# Main.net
KiCad netlist of a schematic drawn in Altium Designer
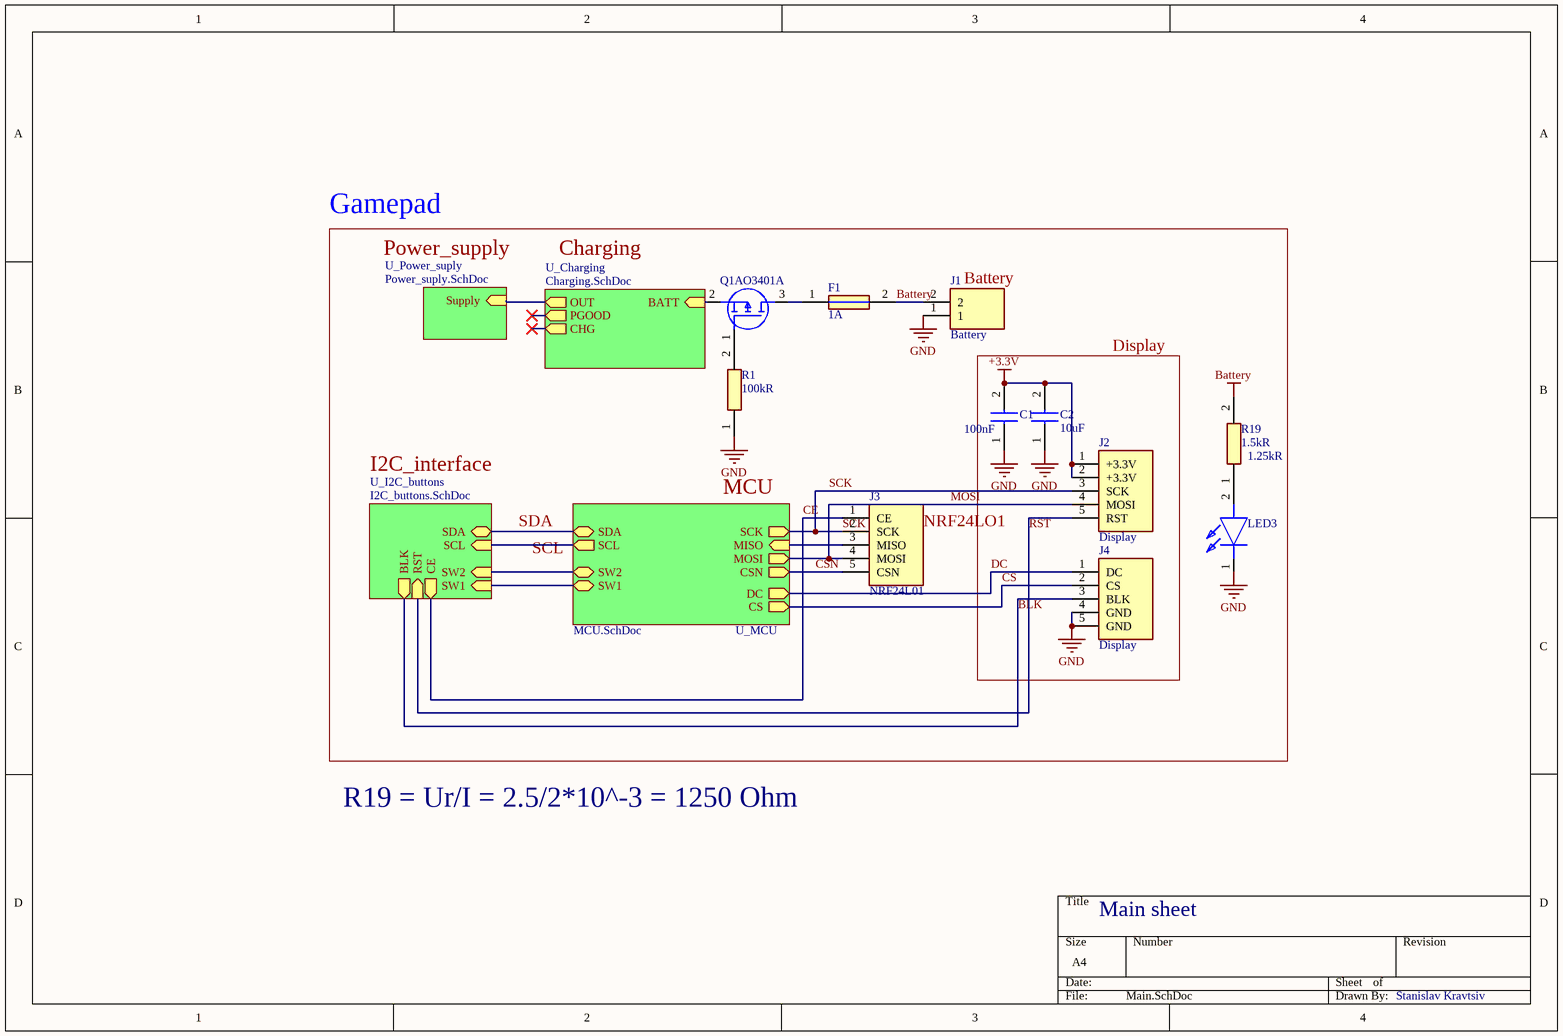
[diagram p0: Main.SchDoc]

(export (version "E")
  (design (tool "Eeschema 10.0.6"))
  (components
    (comp (ref "C1")
      (value "100nF")
      (footprint "SamacSys:CAPC1608X95N")
      (description "Capacitor")
      (fields
        (field (name "MANUFACTURER_PART_NUMBER") "0603B104K500CT")
        (field (name "MOUSER PART NUMBER") "791-0603B104K500CT")
      )
      (libsource (lib "*") (part "0603B104K500CT"))
    )
    (comp (ref "C2")
      (value "10uF")
      (footprint "SamacSys:CAPC2012X140N")
      (description "Capacitor")
      (fields
        (field (name "MANUFACTURER_PART_NUMBER") "CL21B106KPQNNNG")
        (field (name "MOUSER PART NUMBER") "187-CL21B106KPQNNNG")
      )
      (libsource (lib "*") (part "CL21B106KPQNNNG"))
    )
    (comp (ref "F1")
      (value "1А")
      (footprint "SamacSys:FUSC6125X279N")
      (description "Fuse")
      (fields
        (field (name "MANUFACTURER_PART_NUMBER") "0679L2000-01")
        (field (name "MOUSER PART NUMBER") "530-0679L2000-01")
      )
      (libsource (lib "*") (part "0679L2000-01"))
    )
    (comp (ref "J1")
      (value "Battery")
      (footprint "Conector_2")
      (description "Connector")
      (fields
        (field (name "MANUFACTURER_PART_NUMBER") "B2B-XH-AM(LF)(SN)")
        (field (name "MOUSER PART NUMBER") "306-B2B-XH-AMLFSNP")
      )
      (libsource (lib "Gamepad_schem_lib") (part "B2B-XH-AM_LF__SN_"))
    )
    (comp (ref "J2")
      (value "Display")
      (footprint "1.25_JSH-GH_5")
      (description "Connector")
      (fields (field (name "MANUFACTURER_PART_NUMBER") "B5B-XH-AM (LF)(SN)"))
      (libsource (lib "Gamepad_schem_lib") (part "B5B-XH-AM__LF__SN_"))
    )
    (comp (ref "J3")
      (value "NRF24L01")
      (footprint "1.25_JSH-GH_5")
      (description "Connector")
      (fields (field (name "MANUFACTURER_PART_NUMBER") "B5B-XH-AM (LF)(SN)"))
      (libsource (lib "Gamepad_schem_lib") (part "B5B-XH-AM__LF__SN_"))
    )
    (comp (ref "J4")
      (value "Display")
      (footprint "1.25_JSH-GH_5")
      (description "Connector")
      (fields (field (name "MANUFACTURER_PART_NUMBER") "B5B-XH-AM (LF)(SN)"))
      (libsource (lib "Gamepad_schem_lib") (part "B5B-XH-AM__LF__SN_"))
    )
    (comp (ref "LED3")
      (value "LS_L29K-H1J2-1")
      (footprint "SamacSys:SMT-0603")
      (description "LED")
      (fields
        (field (name "MANUFACTURER_PART_NUMBER") "LS L29K-H1J2-1")
        (field (name "MOUSER PART NUMBER") "720-LSL29K-H1J2-1-Z")
      )
      (libsource (lib "*") (part "LS_L29K-H1J2-1"))
    )
    (comp (ref "Q1")
      (value "AO3401A")
      (footprint "SamacSys:SOT95P280X125-3N")
      (description "MOSFET (P-Channel)")
      (libsource (lib "*") (part "AO3401A"))
    )
    (comp (ref "R1")
      (value "100kR")
      (footprint "SamacSys:RESC1608X55N")
      (description "Resistor")
      (fields
        (field (name "MANUFACTURER_PART_NUMBER") "RC0603FR-07100KL")
        (field (name "MOUSER PART NUMBER") "603-RC0603FR-07100KL")
      )
      (libsource (lib "SamacSys") (part "RC0603FR-07100KL"))
    )
    (comp (ref "R19")
      (value "1.5kR")
      (footprint "SamacSys:RESC1608X55N")
      (description "Resistor")
      (fields
        (field (name "MANUFACTURER_PART_NUMBER") "RC0603FR-071K5L")
        (field (name "MOUSER PART NUMBER") "603-RC0603FR-071K5L")
      )
      (libsource (lib "*") (part "RC0603FR-071K5L"))
    )
  )
  (nets
    (net (code "1") (name "+3.3V") (class "Default")
      (node (ref "C1") (pin "2") (pinfunction "2_2") (pintype "passive"))
      (node (ref "C2") (pin "2") (pinfunction "2_2") (pintype "passive"))
      (node (ref "J2") (pin "1") (pinfunction "+3.3V_1") (pintype "passive"))
      (node (ref "J2") (pin "2") (pinfunction "+3.3V_2") (pintype "passive"))
    )
    (net (code "2") (name "/BATT") (class "Default")
      (node (ref "Q1") (pin "2") (pinfunction "S_2") (pintype "passive"))
    )
    (net (code "3") (name "/BLK") (class "Default")
      (node (ref "J4") (pin "3") (pinfunction "SCK_3") (pintype "passive"))
    )
    (net (code "4") (name "/CE") (class "Default")
      (node (ref "J3") (pin "1") (pinfunction "+3.3V_1") (pintype "passive"))
    )
    (net (code "6") (name "/CS") (class "Default")
      (node (ref "J4") (pin "2") (pinfunction "+3.3V_2") (pintype "passive"))
    )
    (net (code "7") (name "/CSN") (class "Default")
      (node (ref "J3") (pin "5") (pinfunction "RST_5") (pintype "passive"))
    )
    (net (code "8") (name "/DC") (class "Default")
      (node (ref "J4") (pin "1") (pinfunction "+3.3V_1") (pintype "passive"))
    )
    (net (code "9") (name "/MISO") (class "Default")
      (node (ref "J3") (pin "3") (pinfunction "SCK_3") (pintype "passive"))
    )
    (net (code "10") (name "/MOSI") (class "Default")
      (node (ref "J2") (pin "4") (pinfunction "MOSI_4") (pintype "passive"))
      (node (ref "J3") (pin "4") (pinfunction "MOSI_4") (pintype "passive"))
    )
    (net (code "13") (name "/RST") (class "Default")
      (node (ref "J2") (pin "5") (pinfunction "RST_5") (pintype "passive"))
    )
    (net (code "14") (name "/SCK") (class "Default")
      (node (ref "J2") (pin "3") (pinfunction "SCK_3") (pintype "passive"))
      (node (ref "J3") (pin "2") (pinfunction "+3.3V_2") (pintype "passive"))
    )
    (net (code "19") (name "Battery") (class "Default")
      (node (ref "F1") (pin "2") (pinfunction "2_2") (pintype "passive"))
      (node (ref "J1") (pin "2") (pinfunction "2_2") (pintype "passive"))
      (node (ref "R19") (pin "2") (pinfunction "2_2") (pintype "passive"))
    )
    (net (code "20") (name "GND") (class "Default")
      (node (ref "C1") (pin "1") (pinfunction "1_1") (pintype "passive"))
      (node (ref "C2") (pin "1") (pinfunction "1_1") (pintype "passive"))
      (node (ref "J1") (pin "1") (pinfunction "1_1") (pintype "passive"))
      (node (ref "J4") (pin "4") (pinfunction "MOSI_4") (pintype "passive"))
      (node (ref "J4") (pin "5") (pinfunction "RST_5") (pintype "passive"))
      (node (ref "LED3") (pin "1") (pinfunction "K_1") (pintype "passive"))
      (node (ref "R1") (pin "1") (pinfunction "1_1") (pintype "passive"))
    )
    (net (code "21") (name "Net-(LED3-A)") (class "Default")
      (node (ref "LED3") (pin "2") (pinfunction "A_2") (pintype "passive"))
      (node (ref "R19") (pin "1") (pinfunction "1_1") (pintype "passive"))
    )
    (net (code "22") (name "Net-(Q1-D)") (class "Default")
      (node (ref "F1") (pin "1") (pinfunction "1_1") (pintype "passive"))
      (node (ref "Q1") (pin "3") (pinfunction "D_3") (pintype "passive"))
    )
    (net (code "23") (name "Net-(Q1-G)") (class "Default")
      (node (ref "Q1") (pin "1") (pinfunction "G_1") (pintype "passive"))
      (node (ref "R1") (pin "2") (pinfunction "2_2") (pintype "passive"))
    )
  )
)
